# hexapod_board_schematics.net
KiCad netlist of a schematic drawn in Altium Designer
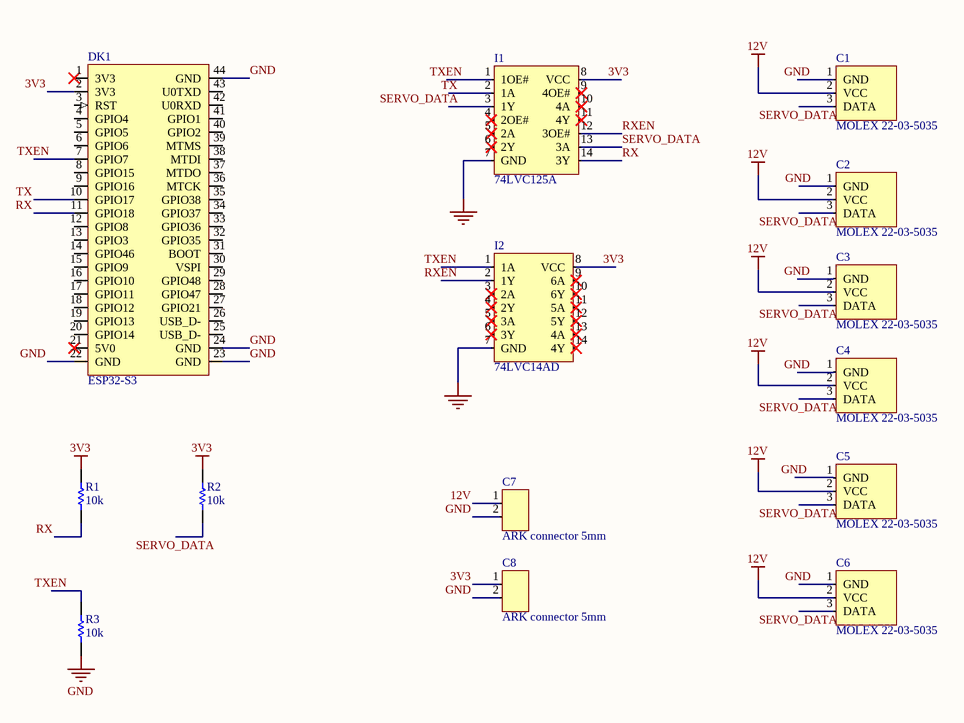
[diagram p0: hexapod_board_schematics.SchDoc]

(export (version "E")
  (design (tool "Eeschema 10.0.6"))
  (components
    (comp (ref "C1")
      (value "MOLEX 22-03-5035")
      (footprint "PCBComponent_1")
      (libsource (lib "Schlib") (part "MOLEX 22-03-5035"))
    )
    (comp (ref "C2")
      (value "MOLEX 22-03-5035")
      (footprint "PCBComponent_1")
      (libsource (lib "Schlib") (part "MOLEX 22-03-5035"))
    )
    (comp (ref "C3")
      (value "MOLEX 22-03-5035")
      (footprint "PCBComponent_1")
      (libsource (lib "Schlib") (part "MOLEX 22-03-5035"))
    )
    (comp (ref "C4")
      (value "MOLEX 22-03-5035")
      (footprint "PCBComponent_1")
      (libsource (lib "Schlib") (part "MOLEX 22-03-5035"))
    )
    (comp (ref "C5")
      (value "MOLEX 22-03-5035")
      (footprint "PCBComponent_1")
      (libsource (lib "Schlib") (part "MOLEX 22-03-5035"))
    )
    (comp (ref "C6")
      (value "MOLEX 22-03-5035")
      (footprint "PCBComponent_1")
      (libsource (lib "Schlib") (part "MOLEX 22-03-5035"))
    )
    (comp (ref "C7")
      (value "ARK connector 5mm")
      (footprint "ARK connector footprint")
      (libsource (lib "Schlib") (part "ARK connector 5mm"))
    )
    (comp (ref "C8")
      (value "ARK connector 5mm")
      (footprint "ARK connector footprint")
      (libsource (lib "Schlib") (part "ARK connector 5mm"))
    )
    (comp (ref "DK1")
      (value "ESP32-S3")
      (footprint "ESP32-S3-DevKit footprint")
      (libsource (lib "Schlib") (part "ESP32-S3-N16R2 DevKit"))
    )
    (comp (ref "I1") (value "74LVC125A") (footprint "SOP14") (libsource (lib "Schlib") (part "74LVC125A")))
    (comp (ref "I2") (value "74LVC14AD") (footprint "SOP14") (libsource (lib "Schlib") (part "74LVC14AD")))
    (comp (ref "R1")
      (value "10k")
      (footprint "RESC2013X60X35ML10T20")
      (fields (field (name "TOLERANCE") "5%") (field (name "MANUFACTURER") "Yageo"))
      (libsource (lib "Altium Content Vault") (part "RES-2"))
    )
    (comp (ref "R2")
      (value "10k")
      (footprint "RESC2013X60X35ML10T20")
      (fields (field (name "TOLERANCE") "5%") (field (name "MANUFACTURER") "Yageo"))
      (libsource (lib "Altium Content Vault") (part "RES-2"))
    )
    (comp (ref "R3")
      (value "10k")
      (footprint "RESC2013X60X35ML10T20")
      (fields (field (name "TOLERANCE") "5%") (field (name "MANUFACTURER") "Yageo"))
      (libsource (lib "Altium Content Vault") (part "RES-2"))
    )
  )
  (nets
    (net (code "1") (name "/RX") (class "Default")
      (node (ref "DK1") (pin "11") (pinfunction "GPIO18_11") (pintype "bidirectional"))
      (node (ref "I1") (pin "14") (pinfunction "3Y_14") (pintype "power_in"))
      (node (ref "R1") (pin "1") (pinfunction "1_1") (pintype "passive"))
    )
    (net (code "2") (name "/RXEN") (class "Default")
      (node (ref "I1") (pin "12") (pinfunction "3OE#_12") (pintype "passive"))
      (node (ref "I2") (pin "2") (pinfunction "1Y_2") (pintype "passive"))
    )
    (net (code "3") (name "/SERVO_DATA") (class "Default")
      (node (ref "C1") (pin "3") (pinfunction "DATA_3") (pintype "passive"))
      (node (ref "C2") (pin "3") (pinfunction "DATA_3") (pintype "passive"))
      (node (ref "C3") (pin "3") (pinfunction "DATA_3") (pintype "passive"))
      (node (ref "C4") (pin "3") (pinfunction "DATA_3") (pintype "passive"))
      (node (ref "C5") (pin "3") (pinfunction "DATA_3") (pintype "passive"))
      (node (ref "C6") (pin "3") (pinfunction "DATA_3") (pintype "passive"))
      (node (ref "I1") (pin "13") (pinfunction "3A_13") (pintype "passive"))
      (node (ref "I1") (pin "3") (pinfunction "1Y_3") (pintype "passive"))
      (node (ref "R2") (pin "1") (pinfunction "1_1") (pintype "passive"))
    )
    (net (code "4") (name "/TX") (class "Default")
      (node (ref "DK1") (pin "10") (pinfunction "GPIO17_10") (pintype "bidirectional"))
      (node (ref "I1") (pin "2") (pinfunction "1A_2") (pintype "passive"))
    )
    (net (code "5") (name "/TXEN") (class "Default")
      (node (ref "DK1") (pin "7") (pinfunction "GPIO7_7") (pintype "bidirectional"))
      (node (ref "I1") (pin "1") (pinfunction "1OE#_1") (pintype "passive"))
      (node (ref "I2") (pin "1") (pinfunction "1A_1") (pintype "passive"))
      (node (ref "R3") (pin "2") (pinfunction "2_2") (pintype "passive"))
    )
    (net (code "6") (name "3V3") (class "Default")
      (node (ref "C8") (pin "1") (pintype "power_in"))
      (node (ref "DK1") (pin "2") (pinfunction "3V3_2") (pintype "power_in"))
      (node (ref "I1") (pin "8") (pinfunction "VCC_8") (pintype "passive"))
      (node (ref "I2") (pin "8") (pinfunction "VCC_8") (pintype "passive"))
      (node (ref "R1") (pin "2") (pinfunction "2_2") (pintype "passive"))
      (node (ref "R2") (pin "2") (pinfunction "2_2") (pintype "passive"))
    )
    (net (code "7") (name "12V") (class "Default")
      (node (ref "C1") (pin "2") (pinfunction "VCC_2") (pintype "power_in"))
      (node (ref "C2") (pin "2") (pinfunction "VCC_2") (pintype "power_in"))
      (node (ref "C3") (pin "2") (pinfunction "VCC_2") (pintype "power_in"))
      (node (ref "C4") (pin "2") (pinfunction "VCC_2") (pintype "power_in"))
      (node (ref "C5") (pin "2") (pinfunction "VCC_2") (pintype "power_in"))
      (node (ref "C6") (pin "2") (pinfunction "VCC_2") (pintype "power_in"))
      (node (ref "C7") (pin "1") (pintype "power_in"))
    )
    (net (code "8") (name "GND") (class "Default")
      (node (ref "C1") (pin "1") (pinfunction "GND_1") (pintype "power_in"))
      (node (ref "C2") (pin "1") (pinfunction "GND_1") (pintype "power_in"))
      (node (ref "C3") (pin "1") (pinfunction "GND_1") (pintype "power_in"))
      (node (ref "C4") (pin "1") (pinfunction "GND_1") (pintype "power_in"))
      (node (ref "C5") (pin "1") (pinfunction "GND_1") (pintype "power_in"))
      (node (ref "C6") (pin "1") (pinfunction "GND_1") (pintype "power_in"))
      (node (ref "C7") (pin "2") (pintype "power_in"))
      (node (ref "C8") (pin "2") (pintype "power_in"))
      (node (ref "DK1") (pin "22") (pinfunction "GND_22") (pintype "power_in"))
      (node (ref "DK1") (pin "23") (pinfunction "GND_23") (pintype "power_in"))
      (node (ref "DK1") (pin "24") (pinfunction "GND_24") (pintype "power_in"))
      (node (ref "DK1") (pin "44") (pinfunction "GND_44") (pintype "power_in"))
      (node (ref "I1") (pin "7") (pinfunction "GND_7") (pintype "power_in"))
      (node (ref "I2") (pin "7") (pinfunction "GND_7") (pintype "power_in"))
      (node (ref "R3") (pin "1") (pinfunction "1_1") (pintype "passive"))
    )
    (net (code "9") (name "unconnected-(DK1-3V3-Pad1)") (class "Default")
      (node (ref "DK1") (pin "1") (pinfunction "3V3_1") (pintype "power_in+no_connect"))
    )
    (net (code "10") (name "unconnected-(DK1-5V0-Pad21)") (class "Default")
      (node (ref "DK1") (pin "21") (pinfunction "5V0_21") (pintype "power_in+no_connect"))
    )
    (net (code "11") (name "unconnected-(DK1-BOOT-Pad31)") (class "Default")
      (node (ref "DK1") (pin "31") (pinfunction "BOOT_31") (pintype "bidirectional"))
    )
    (net (code "12") (name "unconnected-(DK1-GPIO1-Pad41)") (class "Default")
      (node (ref "DK1") (pin "41") (pinfunction "GPIO1_41") (pintype "bidirectional"))
    )
    (net (code "13") (name "unconnected-(DK1-GPIO2-Pad40)") (class "Default")
      (node (ref "DK1") (pin "40") (pinfunction "GPIO2_40") (pintype "bidirectional"))
    )
    (net (code "14") (name "unconnected-(DK1-GPIO3-Pad13)") (class "Default")
      (node (ref "DK1") (pin "13") (pinfunction "GPIO3_13") (pintype "bidirectional"))
    )
    (net (code "15") (name "unconnected-(DK1-GPIO4-Pad4)") (class "Default")
      (node (ref "DK1") (pin "4") (pinfunction "GPIO4_4") (pintype "bidirectional"))
    )
    (net (code "16") (name "unconnected-(DK1-GPIO5-Pad5)") (class "Default")
      (node (ref "DK1") (pin "5") (pinfunction "GPIO5_5") (pintype "bidirectional"))
    )
    (net (code "17") (name "unconnected-(DK1-GPIO6-Pad6)") (class "Default")
      (node (ref "DK1") (pin "6") (pinfunction "GPIO6_6") (pintype "bidirectional"))
    )
    (net (code "18") (name "unconnected-(DK1-GPIO8-Pad12)") (class "Default")
      (node (ref "DK1") (pin "12") (pinfunction "GPIO8_12") (pintype "bidirectional"))
    )
    (net (code "19") (name "unconnected-(DK1-GPIO9-Pad15)") (class "Default")
      (node (ref "DK1") (pin "15") (pinfunction "GPIO9_15") (pintype "bidirectional"))
    )
    (net (code "20") (name "unconnected-(DK1-GPIO10-Pad16)") (class "Default")
      (node (ref "DK1") (pin "16") (pinfunction "GPIO10_16") (pintype "bidirectional"))
    )
    (net (code "21") (name "unconnected-(DK1-GPIO11-Pad17)") (class "Default")
      (node (ref "DK1") (pin "17") (pinfunction "GPIO11_17") (pintype "bidirectional"))
    )
    (net (code "22") (name "unconnected-(DK1-GPIO12-Pad18)") (class "Default")
      (node (ref "DK1") (pin "18") (pinfunction "GPIO12_18") (pintype "bidirectional"))
    )
    (net (code "23") (name "unconnected-(DK1-GPIO13-Pad19)") (class "Default")
      (node (ref "DK1") (pin "19") (pinfunction "GPIO13_19") (pintype "bidirectional"))
    )
    (net (code "24") (name "unconnected-(DK1-GPIO14-Pad20)") (class "Default")
      (node (ref "DK1") (pin "20") (pinfunction "GPIO14_20") (pintype "bidirectional"))
    )
    (net (code "25") (name "unconnected-(DK1-GPIO15-Pad8)") (class "Default")
      (node (ref "DK1") (pin "8") (pinfunction "GPIO15_8") (pintype "bidirectional"))
    )
    (net (code "26") (name "unconnected-(DK1-GPIO16-Pad9)") (class "Default")
      (node (ref "DK1") (pin "9") (pinfunction "GPIO16_9") (pintype "bidirectional"))
    )
    (net (code "27") (name "unconnected-(DK1-GPIO21-Pad27)") (class "Default")
      (node (ref "DK1") (pin "27") (pinfunction "GPIO21_27") (pintype "bidirectional"))
    )
    (net (code "28") (name "unconnected-(DK1-GPIO35-Pad32)") (class "Default")
      (node (ref "DK1") (pin "32") (pinfunction "GPIO35_32") (pintype "bidirectional"))
    )
    (net (code "29") (name "unconnected-(DK1-GPIO36-Pad33)") (class "Default")
      (node (ref "DK1") (pin "33") (pinfunction "GPIO36_33") (pintype "bidirectional"))
    )
    (net (code "30") (name "unconnected-(DK1-GPIO37-Pad34)") (class "Default")
      (node (ref "DK1") (pin "34") (pinfunction "GPIO37_34") (pintype "bidirectional"))
    )
    (net (code "31") (name "unconnected-(DK1-GPIO38-Pad35)") (class "Default")
      (node (ref "DK1") (pin "35") (pinfunction "GPIO38_35") (pintype "bidirectional"))
    )
    (net (code "32") (name "unconnected-(DK1-GPIO46-Pad14)") (class "Default")
      (node (ref "DK1") (pin "14") (pinfunction "GPIO46_14") (pintype "bidirectional"))
    )
    (net (code "33") (name "unconnected-(DK1-GPIO47-Pad28)") (class "Default")
      (node (ref "DK1") (pin "28") (pinfunction "GPIO47_28") (pintype "bidirectional"))
    )
    (net (code "34") (name "unconnected-(DK1-GPIO48-Pad29)") (class "Default")
      (node (ref "DK1") (pin "29") (pinfunction "GPIO48_29") (pintype "bidirectional"))
    )
    (net (code "35") (name "unconnected-(DK1-MTCK-Pad36)") (class "Default")
      (node (ref "DK1") (pin "36") (pinfunction "MTCK_36") (pintype "bidirectional"))
    )
    (net (code "36") (name "unconnected-(DK1-MTDI-Pad38)") (class "Default")
      (node (ref "DK1") (pin "38") (pinfunction "MTDI_38") (pintype "bidirectional"))
    )
    (net (code "37") (name "unconnected-(DK1-MTDO-Pad37)") (class "Default")
      (node (ref "DK1") (pin "37") (pinfunction "MTDO_37") (pintype "bidirectional"))
    )
    (net (code "38") (name "unconnected-(DK1-MTMS-Pad39)") (class "Default")
      (node (ref "DK1") (pin "39") (pinfunction "MTMS_39") (pintype "bidirectional"))
    )
    (net (code "39") (name "unconnected-(DK1-RST-Pad3)") (class "Default")
      (node (ref "DK1") (pin "3") (pinfunction "RST_3") (pintype "input"))
    )
    (net (code "40") (name "unconnected-(DK1-U0RXD-Pad42)") (class "Default")
      (node (ref "DK1") (pin "42") (pinfunction "U0RXD_42") (pintype "bidirectional"))
    )
    (net (code "41") (name "unconnected-(DK1-U0TXD-Pad43)") (class "Default")
      (node (ref "DK1") (pin "43") (pinfunction "U0TXD_43") (pintype "bidirectional"))
    )
    (net (code "42") (name "unconnected-(DK1-USB_D--Pad25)") (class "Default")
      (node (ref "DK1") (pin "25") (pinfunction "USB_D-_25") (pintype "bidirectional"))
    )
    (net (code "43") (name "unconnected-(DK1-USB_D--Pad26)") (class "Default")
      (node (ref "DK1") (pin "26") (pinfunction "USB_D-_26") (pintype "bidirectional"))
    )
    (net (code "44") (name "unconnected-(DK1-VSPI-Pad30)") (class "Default")
      (node (ref "DK1") (pin "30") (pinfunction "VSPI_30") (pintype "bidirectional"))
    )
    (net (code "45") (name "unconnected-(I1-2A-Pad5)") (class "Default")
      (node (ref "I1") (pin "5") (pinfunction "2A_5") (pintype "passive+no_connect"))
    )
    (net (code "46") (name "unconnected-(I1-2OE#-Pad4)") (class "Default")
      (node (ref "I1") (pin "4") (pinfunction "2OE#_4") (pintype "passive+no_connect"))
    )
    (net (code "47") (name "unconnected-(I1-2Y-Pad6)") (class "Default")
      (node (ref "I1") (pin "6") (pinfunction "2Y_6") (pintype "passive+no_connect"))
    )
    (net (code "48") (name "unconnected-(I1-4A-Pad10)") (class "Default")
      (node (ref "I1") (pin "10") (pinfunction "4A_10") (pintype "passive+no_connect"))
    )
    (net (code "49") (name "unconnected-(I1-4OE#-Pad9)") (class "Default")
      (node (ref "I1") (pin "9") (pinfunction "4OE#_9") (pintype "passive+no_connect"))
    )
    (net (code "50") (name "unconnected-(I1-4Y-Pad11)") (class "Default")
      (node (ref "I1") (pin "11") (pinfunction "4Y_11") (pintype "passive+no_connect"))
    )
    (net (code "51") (name "unconnected-(I2-2A-Pad3)") (class "Default")
      (node (ref "I2") (pin "3") (pinfunction "2A_3") (pintype "passive+no_connect"))
    )
    (net (code "52") (name "unconnected-(I2-2Y-Pad4)") (class "Default")
      (node (ref "I2") (pin "4") (pinfunction "2Y_4") (pintype "passive+no_connect"))
    )
    (net (code "53") (name "unconnected-(I2-3A-Pad5)") (class "Default")
      (node (ref "I2") (pin "5") (pinfunction "3A_5") (pintype "passive+no_connect"))
    )
    (net (code "54") (name "unconnected-(I2-3Y-Pad6)") (class "Default")
      (node (ref "I2") (pin "6") (pinfunction "3Y_6") (pintype "passive+no_connect"))
    )
    (net (code "55") (name "unconnected-(I2-4A-Pad13)") (class "Default")
      (node (ref "I2") (pin "13") (pinfunction "4A_13") (pintype "passive+no_connect"))
    )
    (net (code "56") (name "unconnected-(I2-4Y-Pad14)") (class "Default")
      (node (ref "I2") (pin "14") (pinfunction "4Y_14") (pintype "power_in+no_connect"))
    )
    (net (code "57") (name "unconnected-(I2-5A-Pad11)") (class "Default")
      (node (ref "I2") (pin "11") (pinfunction "5A_11") (pintype "passive+no_connect"))
    )
    (net (code "58") (name "unconnected-(I2-5Y-Pad12)") (class "Default")
      (node (ref "I2") (pin "12") (pinfunction "5Y_12") (pintype "passive+no_connect"))
    )
    (net (code "59") (name "unconnected-(I2-6A-Pad9)") (class "Default")
      (node (ref "I2") (pin "9") (pinfunction "6A_9") (pintype "passive+no_connect"))
    )
    (net (code "60") (name "unconnected-(I2-6Y-Pad10)") (class "Default")
      (node (ref "I2") (pin "10") (pinfunction "6Y_10") (pintype "passive+no_connect"))
    )
  )
)
